# flashlight.net
KiCad netlist of a schematic drawn in EAGLE
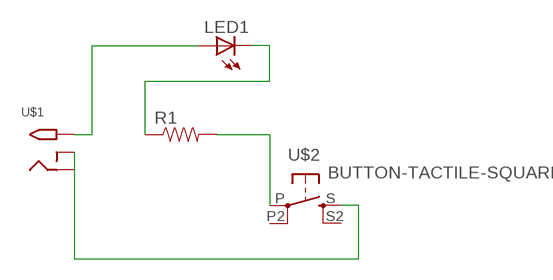
[diagram p0: schematic, sheet 1]

(export (version "E")
  (design (tool "Eeschema 10.0.6"))
  (components
    (comp (ref "LED1")
      (value "LED5MM")
      (footprint "eagle-import:LED5MM")
      (libsource (lib "eagle-import") (part "LED5MM"))
    )
    (comp (ref "R1")
      (value "RESISTORAXIAL-0.3")
      (footprint "eagle-import:AXIAL-0.3")
      (libsource (lib "eagle-import") (part "RESISTORAXIAL-0.3"))
    )
    (comp (ref "U$1")
      (value "2.1MMJACKTHM")
      (footprint "eagle-import:PJ-102A")
      (libsource (lib "eagle-import") (part "2.1MMJACKTHM"))
    )
    (comp (ref "U$2")
      (value "BUTTON-TACTILE-SQUARE")
      (footprint "eagle-import:BUTTON-TACTILE-SQUARE-ADAFRUIT1010")
      (libsource (lib "eagle-import") (part "BUTTON-TACTILE-SQUARE"))
    )
  )
  (nets
    (net (code "1") (name "Net-(LED1-C)") (class "Default")
      (node (ref "LED1") (pin "K") (pinfunction "C_K") (pintype "passive"))
      (node (ref "R1") (pin "P$1") (pinfunction "1_P$1") (pintype "passive"))
    )
    (net (code "2") (name "Net-(LED1-PadA)") (class "Default")
      (node (ref "LED1") (pin "A") (pinfunction "A_A") (pintype "passive"))
      (node (ref "U$1") (pin "TIP") (pinfunction "TIP_TIP") (pintype "bidirectional"))
    )
    (net (code "3") (name "Net-(R1-2)") (class "Default")
      (node (ref "R1") (pin "P$2") (pinfunction "2_P$2") (pintype "passive"))
      (node (ref "U$2") (pin "P") (pinfunction "P_P") (pintype "passive"))
    )
    (net (code "4") (name "Net-(U$1-PadRING)") (class "Default")
      (node (ref "U$1") (pin "RING") (pinfunction "RING_RING") (pintype "bidirectional"))
      (node (ref "U$1") (pin "RING_SW") (pinfunction "RING_SW_RING_SW") (pintype "bidirectional"))
      (node (ref "U$2") (pin "S") (pinfunction "S_S") (pintype "passive"))
    )
    (net (code "5") (name "unconnected-(U$2-P1-PadP2)") (class "Default")
      (node (ref "U$2") (pin "P2") (pinfunction "P1_P2") (pintype "passive"))
    )
    (net (code "6") (name "unconnected-(U$2-S1-PadS2)") (class "Default")
      (node (ref "U$2") (pin "S2") (pinfunction "S1_S2") (pintype "passive"))
    )
  )
)
